# Teensy.net
KiCad netlist of a schematic drawn in Altium Designer
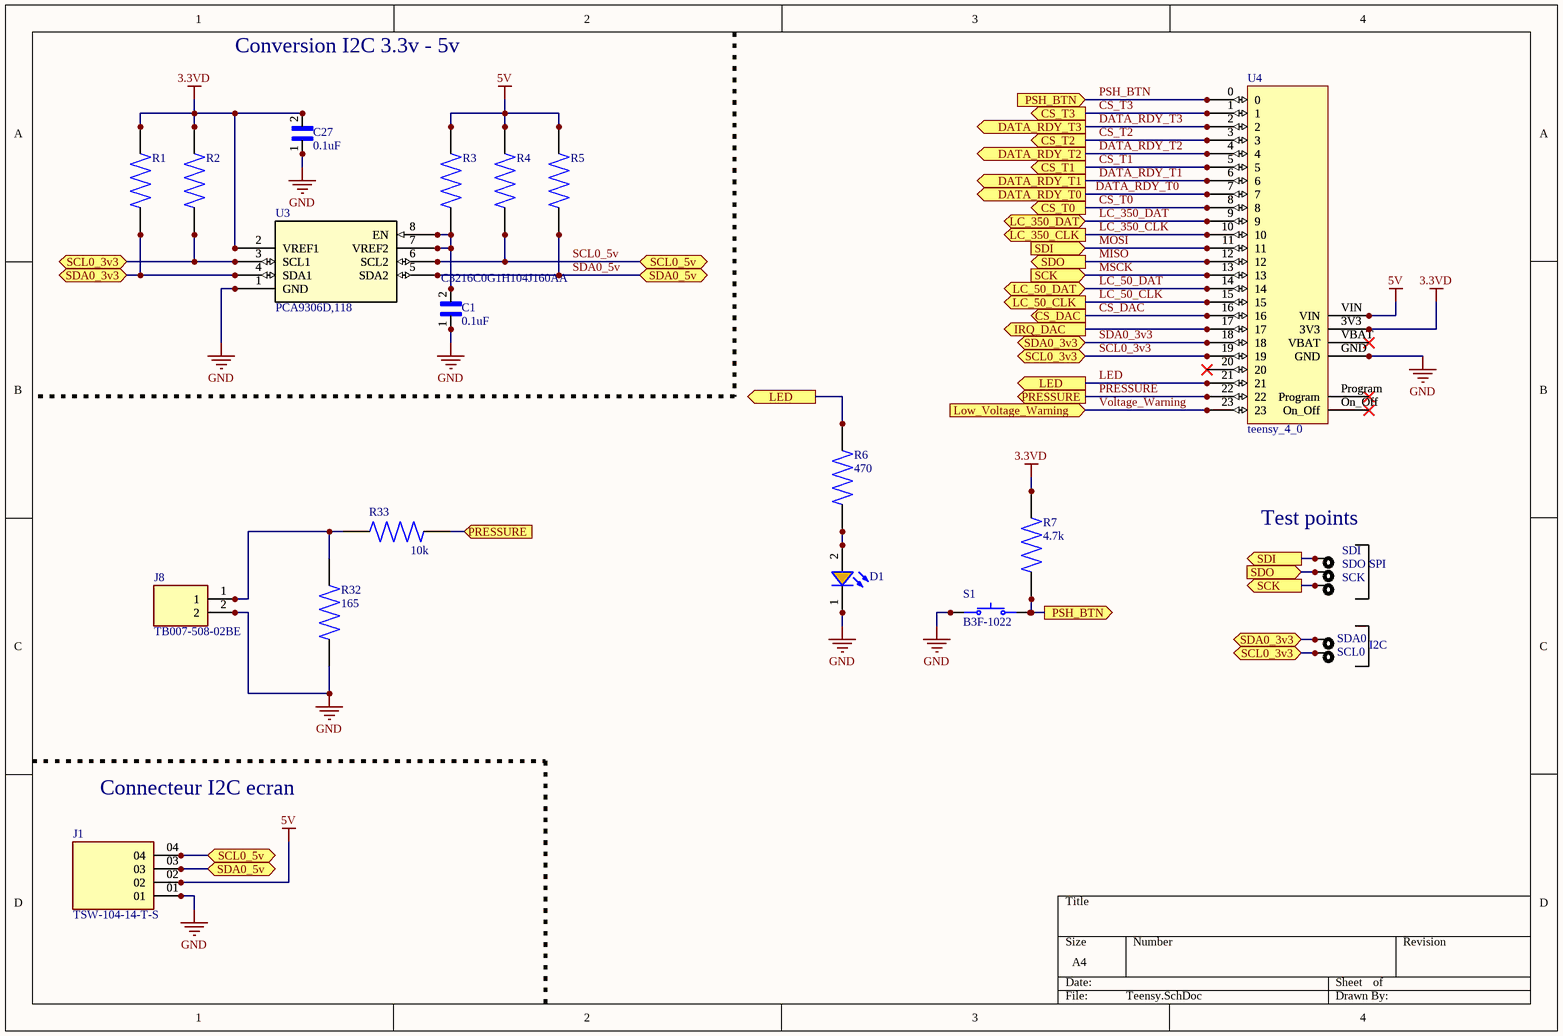
[diagram p0: Teensy.SchDoc]

(export (version "E")
  (design (tool "Eeschema 10.0.6"))
  (components
    (comp (ref "C1")
      (value "C3216C0G1H104J160AA")
      (footprint "C3216C0G1H104J160AA")
      (fields (field (name "ALTIUM_VALUE") "0.1uF"))
      (libsource (lib "C3216C0G1H104J160AA") (part "C3216C0G1H104J160AA"))
    )
    (comp (ref "C27")
      (value "0.1uF")
      (footprint "C3216C0G1H104J160AA")
      (fields (field (name "Comment") "C3216C0G1H104J160AA"))
      (libsource (lib "C3216C0G1H104J160AA") (part "C3216C0G1H104J160AA"))
    )
    (comp (ref "D1")
      (value "150120YS75000")
      (footprint "150120YS75000")
      (description "Yellow 590nm LED Indication - Discrete 2V 1206 (3216 Metric)")
      (libsource (lib "150120YS75000") (part "150120YS75000"))
    )
    (comp (ref "J1")
      (value "TSW-104-14-T-S")
      (footprint "TSW-104-14-T-S")
      (libsource (lib "TSW-104-14-T-S") (part "TSW-104-14-T-S"))
    )
    (comp (ref "J8")
      (value "TB007-508-02BE")
      (footprint "CUI_TB007-508-02BE")
      (description "2~24 Poles, Screw Type, Horizontal, 5.08 Pitch, 24~12 _AWG_, Terminal Block Connector")
      (fields (field (name "MF") "CUI Devices"))
      (libsource (lib "TB007-508-02BE") (part "TB007-508-02BE"))
    )
    (comp (ref "R1")
      (value "ESR10EZPJ222")
      (footprint "RESC2012X65N")
      (fields (field (name "MF") "Rohm") (field (name "DIGI-KEY_PART_NUMBER") "RHM2.2KKCT-ND"))
      (libsource (lib "ESR10EZPJ222") (part "ESR10EZPJ222"))
    )
    (comp (ref "R2")
      (value "ESR10EZPJ222")
      (footprint "RESC2012X65N")
      (fields (field (name "MF") "Rohm") (field (name "DIGI-KEY_PART_NUMBER") "RHM2.2KKCT-ND"))
      (libsource (lib "ESR10EZPJ222") (part "ESR10EZPJ222"))
    )
    (comp (ref "R3")
      (value "ERJ-6GEYJ204V")
      (footprint "RESC2012X70N")
      (description "Resistor;Thick Film;Res 200 Kilohms;Pwr-Rtg 0.125 W;Tol 5%;SMT;0805;Tape & Reel")
      (libsource (lib "ERJ-6GEYJ204V") (part "ERJ-6GEYJ204V"))
    )
    (comp (ref "R4")
      (value "ESR10EZPJ222")
      (footprint "RESC2012X65N")
      (fields (field (name "MF") "Rohm") (field (name "DIGI-KEY_PART_NUMBER") "RHM2.2KKCT-ND"))
      (libsource (lib "ESR10EZPJ222") (part "ESR10EZPJ222"))
    )
    (comp (ref "R5")
      (value "ESR10EZPJ222")
      (footprint "RESC2012X65N")
      (fields (field (name "MF") "Rohm") (field (name "DIGI-KEY_PART_NUMBER") "RHM2.2KKCT-ND"))
      (libsource (lib "ESR10EZPJ222") (part "ESR10EZPJ222"))
    )
    (comp (ref "R6")
      (value "470")
      (footprint "RMCF1206JT470R")
      (description "RES 470 OHM 5% 1/4W 1206")
      (fields (field (name "Comment") "RMCF1206JT470R"))
      (libsource (lib "RMCF1206JT470R") (part "RMCF1206JT470R"))
    )
    (comp (ref "R7")
      (value "4.7k")
      (footprint "CRGH0805F4K7")
      (description "CRGH0805 1% 4K7 0.33W")
      (fields (field (name "TOLERANCE") "±1%") (field (name "Comment") "CRGH0805F4K7"))
      (libsource (lib "CRGH0805F4K7") (part "CRGH0805F4K7"))
    )
    (comp (ref "R32")
      (value "165")
      (footprint "RC1206FR-07165RL")
      (description "165 Ohms ±1% 0.25W, 1/4W Chip Resistor 1206 (3216 Metric) Moisture Resistant Thick Film")
      (fields (field (name "TOLERANCE") "±1%") (field (name "Comment") "RC1206FR-07165RL"))
      (libsource (lib "RC1206FR-07165RL") (part "RC1206FR-07165RL"))
    )
    (comp (ref "R33")
      (value "10k")
      (footprint "ERJ-P06J103V")
      (description "RES SMD 10K OHM 5% 1/2W 0805")
      (fields (field (name "TOLERANCE") "±5%") (field (name "Comment") "ERJ-P06J103V"))
      (libsource (lib "ERJ-P06J103V") (part "ERJ-P06J103V"))
    )
    (comp (ref "S1")
      (value "B3F-1022")
      (footprint "B3F-1022")
      (description "SWITCH TACTILE SPST-NO 0.05A 24V")
      (libsource (lib "B3F-1022") (part "B3F-1022"))
    )
    (comp (ref "SCK")
      (value "RCS-0C")
      (footprint "RCS-0C")
      (description "PC TEST POINT NATURAL")
      (libsource (lib "RCS-0C") (part "RCS-0C"))
    )
    (comp (ref "SCL0")
      (value "RCS-0C")
      (footprint "RCS-0C")
      (description "PC TEST POINT NATURAL")
      (libsource (lib "RCS-0C") (part "RCS-0C"))
    )
    (comp (ref "SDA0")
      (value "RCS-0C")
      (footprint "RCS-0C")
      (description "PC TEST POINT NATURAL")
      (libsource (lib "RCS-0C") (part "RCS-0C"))
    )
    (comp (ref "SDI")
      (value "RCS-0C")
      (footprint "RCS-0C")
      (description "PC TEST POINT NATURAL")
      (libsource (lib "RCS-0C") (part "RCS-0C"))
    )
    (comp (ref "SDO")
      (value "RCS-0C")
      (footprint "RCS-0C")
      (description "PC TEST POINT NATURAL")
      (libsource (lib "RCS-0C") (part "RCS-0C"))
    )
    (comp (ref "U3")
      (value "PCA9306D,118")
      (footprint "SO8_SOT96-1_NXP")
      (description "No Description Available")
      (fields (field (name "COPYRIGHT") "Copyright (C) 2018 Accelerated Designs. All rights reserved"))
      (libsource (lib "PCA9306D") (part "PCA9306D,118"))
    )
    (comp (ref "U4")
      (value "teensy_4_0")
      (footprint "teensy_4_0")
      (libsource (lib "teensy_4_0") (part "teensy_4_0"))
    )
  )
  (nets
    (net (code "1") (name "/CS_DAC") (class "Default")
      (node (ref "U4") (pin "16") (pinfunction "16_16") (pintype "bidirectional"))
    )
    (net (code "2") (name "/CS_T0") (class "Default")
      (node (ref "U4") (pin "8") (pinfunction "8_8") (pintype "bidirectional"))
    )
    (net (code "3") (name "/CS_T1") (class "Default")
      (node (ref "U4") (pin "5") (pinfunction "5_5") (pintype "bidirectional"))
    )
    (net (code "4") (name "/CS_T2") (class "Default")
      (node (ref "U4") (pin "3") (pinfunction "3_3") (pintype "bidirectional"))
    )
    (net (code "5") (name "/CS_T3") (class "Default")
      (node (ref "U4") (pin "1") (pinfunction "1_1") (pintype "bidirectional"))
    )
    (net (code "6") (name "/DATA_RDY_T0") (class "Default")
      (node (ref "U4") (pin "7") (pinfunction "7_7") (pintype "bidirectional"))
    )
    (net (code "7") (name "/DATA_RDY_T1") (class "Default")
      (node (ref "U4") (pin "6") (pinfunction "6_6") (pintype "bidirectional"))
    )
    (net (code "8") (name "/DATA_RDY_T2") (class "Default")
      (node (ref "U4") (pin "4") (pinfunction "4_4") (pintype "bidirectional"))
    )
    (net (code "9") (name "/DATA_RDY_T3") (class "Default")
      (node (ref "U4") (pin "2") (pinfunction "2_2") (pintype "bidirectional"))
    )
    (net (code "10") (name "/IRQ_DAC") (class "Default")
      (node (ref "U4") (pin "17") (pinfunction "17_17") (pintype "bidirectional"))
    )
    (net (code "11") (name "/LC_50_CLK") (class "Default")
      (node (ref "U4") (pin "15") (pinfunction "15_15") (pintype "bidirectional"))
    )
    (net (code "12") (name "/LC_50_DAT") (class "Default")
      (node (ref "U4") (pin "14") (pinfunction "14_14") (pintype "bidirectional"))
    )
    (net (code "13") (name "/LC_350_CLK") (class "Default")
      (node (ref "U4") (pin "10") (pinfunction "10_10") (pintype "bidirectional"))
    )
    (net (code "14") (name "/LC_350_DAT") (class "Default")
      (node (ref "U4") (pin "9") (pinfunction "9_9") (pintype "bidirectional"))
    )
    (net (code "15") (name "/LED") (class "Default")
      (node (ref "R6") (pin "2") (pinfunction "2_2") (pintype "passive"))
      (node (ref "U4") (pin "21") (pinfunction "21_21") (pintype "bidirectional"))
    )
    (net (code "16") (name "/MISO") (class "Default")
      (node (ref "SDO") (pin "1") (pinfunction "1_1") (pintype "passive"))
      (node (ref "U4") (pin "12") (pinfunction "12_12") (pintype "bidirectional"))
    )
    (net (code "17") (name "/MOSI") (class "Default")
      (node (ref "SDI") (pin "1") (pinfunction "1_1") (pintype "passive"))
      (node (ref "U4") (pin "11") (pinfunction "11_11") (pintype "bidirectional"))
    )
    (net (code "18") (name "/MSCK") (class "Default")
      (node (ref "SCK") (pin "1") (pinfunction "1_1") (pintype "passive"))
      (node (ref "U4") (pin "13") (pinfunction "13_13") (pintype "bidirectional"))
    )
    (net (code "19") (name "/PRESSURE") (class "Default")
      (node (ref "R33") (pin "2") (pinfunction "2_2") (pintype "passive"))
      (node (ref "U4") (pin "22") (pinfunction "22_22") (pintype "bidirectional"))
    )
    (net (code "20") (name "/PSH_BTN") (class "Default")
      (node (ref "R7") (pin "1") (pinfunction "1_1") (pintype "passive"))
      (node (ref "S1") (pin "3") (pinfunction "NO_3") (pintype "passive"))
      (node (ref "U4") (pin "0") (pinfunction "0_0") (pintype "bidirectional"))
    )
    (net (code "21") (name "/SCL0_3v3") (class "Default")
      (node (ref "R2") (pin "1") (pinfunction "1_1") (pintype "passive"))
      (node (ref "SCL0") (pin "1") (pinfunction "1_1") (pintype "passive"))
      (node (ref "U3") (pin "3") (pinfunction "SCL1_3") (pintype "bidirectional"))
      (node (ref "U4") (pin "19") (pinfunction "19_19") (pintype "bidirectional"))
    )
    (net (code "22") (name "/SCL0_5v") (class "Default")
      (node (ref "J1") (pin "04") (pinfunction "04_04") (pintype "passive"))
      (node (ref "R4") (pin "1") (pinfunction "1_1") (pintype "passive"))
      (node (ref "U3") (pin "6") (pinfunction "SCL2_6") (pintype "bidirectional"))
    )
    (net (code "23") (name "/SDA0_3v3") (class "Default")
      (node (ref "R1") (pin "1") (pinfunction "1_1") (pintype "passive"))
      (node (ref "SDA0") (pin "1") (pinfunction "1_1") (pintype "passive"))
      (node (ref "U3") (pin "4") (pinfunction "SDA1_4") (pintype "bidirectional"))
      (node (ref "U4") (pin "18") (pinfunction "18_18") (pintype "bidirectional"))
    )
    (net (code "24") (name "/SDA0_5v") (class "Default")
      (node (ref "J1") (pin "03") (pinfunction "03_03") (pintype "passive"))
      (node (ref "R5") (pin "1") (pinfunction "1_1") (pintype "passive"))
      (node (ref "U3") (pin "5") (pinfunction "SDA2_5") (pintype "bidirectional"))
    )
    (net (code "25") (name "/Voltage_Warning") (class "Default")
      (node (ref "U4") (pin "23") (pinfunction "23_23") (pintype "bidirectional"))
    )
    (net (code "26") (name "3.3VD") (class "Default")
      (node (ref "C27") (pin "2") (pinfunction "2_2") (pintype "passive"))
      (node (ref "R1") (pin "2") (pinfunction "2_2") (pintype "passive"))
      (node (ref "R2") (pin "2") (pinfunction "2_2") (pintype "passive"))
      (node (ref "R7") (pin "2") (pinfunction "2_2") (pintype "passive"))
      (node (ref "U3") (pin "2") (pinfunction "VREF1_2") (pintype "power_in"))
      (node (ref "U4") (pin "3V3") (pinfunction "3V3_3V3") (pintype "power_in"))
    )
    (net (code "27") (name "5V") (class "Default")
      (node (ref "J1") (pin "02") (pinfunction "02_02") (pintype "passive"))
      (node (ref "R3") (pin "2") (pinfunction "2_2") (pintype "passive"))
      (node (ref "R4") (pin "2") (pinfunction "2_2") (pintype "passive"))
      (node (ref "R5") (pin "2") (pinfunction "2_2") (pintype "passive"))
      (node (ref "U4") (pin "VIN") (pinfunction "VIN_VIN") (pintype "power_in"))
    )
    (net (code "28") (name "GND") (class "Default")
      (node (ref "C1") (pin "1") (pinfunction "1_1") (pintype "passive"))
      (node (ref "C27") (pin "1") (pinfunction "1_1") (pintype "passive"))
      (node (ref "D1") (pin "1") (pinfunction "K_1") (pintype "passive"))
      (node (ref "J1") (pin "01") (pinfunction "01_01") (pintype "passive"))
      (node (ref "J8") (pin "2") (pinfunction "2_2") (pintype "passive"))
      (node (ref "R32") (pin "1") (pinfunction "1_1") (pintype "passive"))
      (node (ref "S1") (pin "1") (pinfunction "COM_1") (pintype "passive"))
      (node (ref "U3") (pin "1") (pinfunction "GND_1") (pintype "passive"))
      (node (ref "U4") (pin "GND") (pinfunction "GND_GND") (pintype "power_in"))
    )
    (net (code "29") (name "Net-(D1-A)") (class "Default")
      (node (ref "D1") (pin "2") (pinfunction "A_2") (pintype "passive"))
      (node (ref "R6") (pin "1") (pinfunction "1_1") (pintype "passive"))
    )
    (net (code "30") (name "Net-(J8-Pad1)") (class "Default")
      (node (ref "J8") (pin "1") (pinfunction "1_1") (pintype "passive"))
      (node (ref "R32") (pin "2") (pinfunction "2_2") (pintype "passive"))
      (node (ref "R33") (pin "1") (pinfunction "1_1") (pintype "passive"))
    )
    (net (code "31") (name "Net-(U3-EN)") (class "Default")
      (node (ref "C1") (pin "2") (pinfunction "2_2") (pintype "passive"))
      (node (ref "R3") (pin "1") (pinfunction "1_1") (pintype "passive"))
      (node (ref "U3") (pin "7") (pinfunction "VREF2_7") (pintype "power_in"))
      (node (ref "U3") (pin "8") (pinfunction "EN_8") (pintype "input"))
    )
    (net (code "32") (name "unconnected-(U4-Pad20)") (class "Default")
      (node (ref "U4") (pin "20") (pinfunction "20_20") (pintype "bidirectional+no_connect"))
    )
    (net (code "33") (name "unconnected-(U4-PadOn_Off)") (class "Default")
      (node (ref "U4") (pin "On_Off") (pinfunction "On_Off_On_Off") (pintype "power_in+no_connect"))
    )
    (net (code "34") (name "unconnected-(U4-PadProgram)") (class "Default")
      (node (ref "U4") (pin "Program") (pinfunction "Program_Program") (pintype "power_in+no_connect"))
    )
    (net (code "35") (name "unconnected-(U4-PadVBAT)") (class "Default")
      (node (ref "U4") (pin "VBAT") (pinfunction "VBAT_VBAT") (pintype "power_in+no_connect"))
    )
  )
)
